# Oscilador.net
KiCad netlist of a schematic drawn in Altium Designer
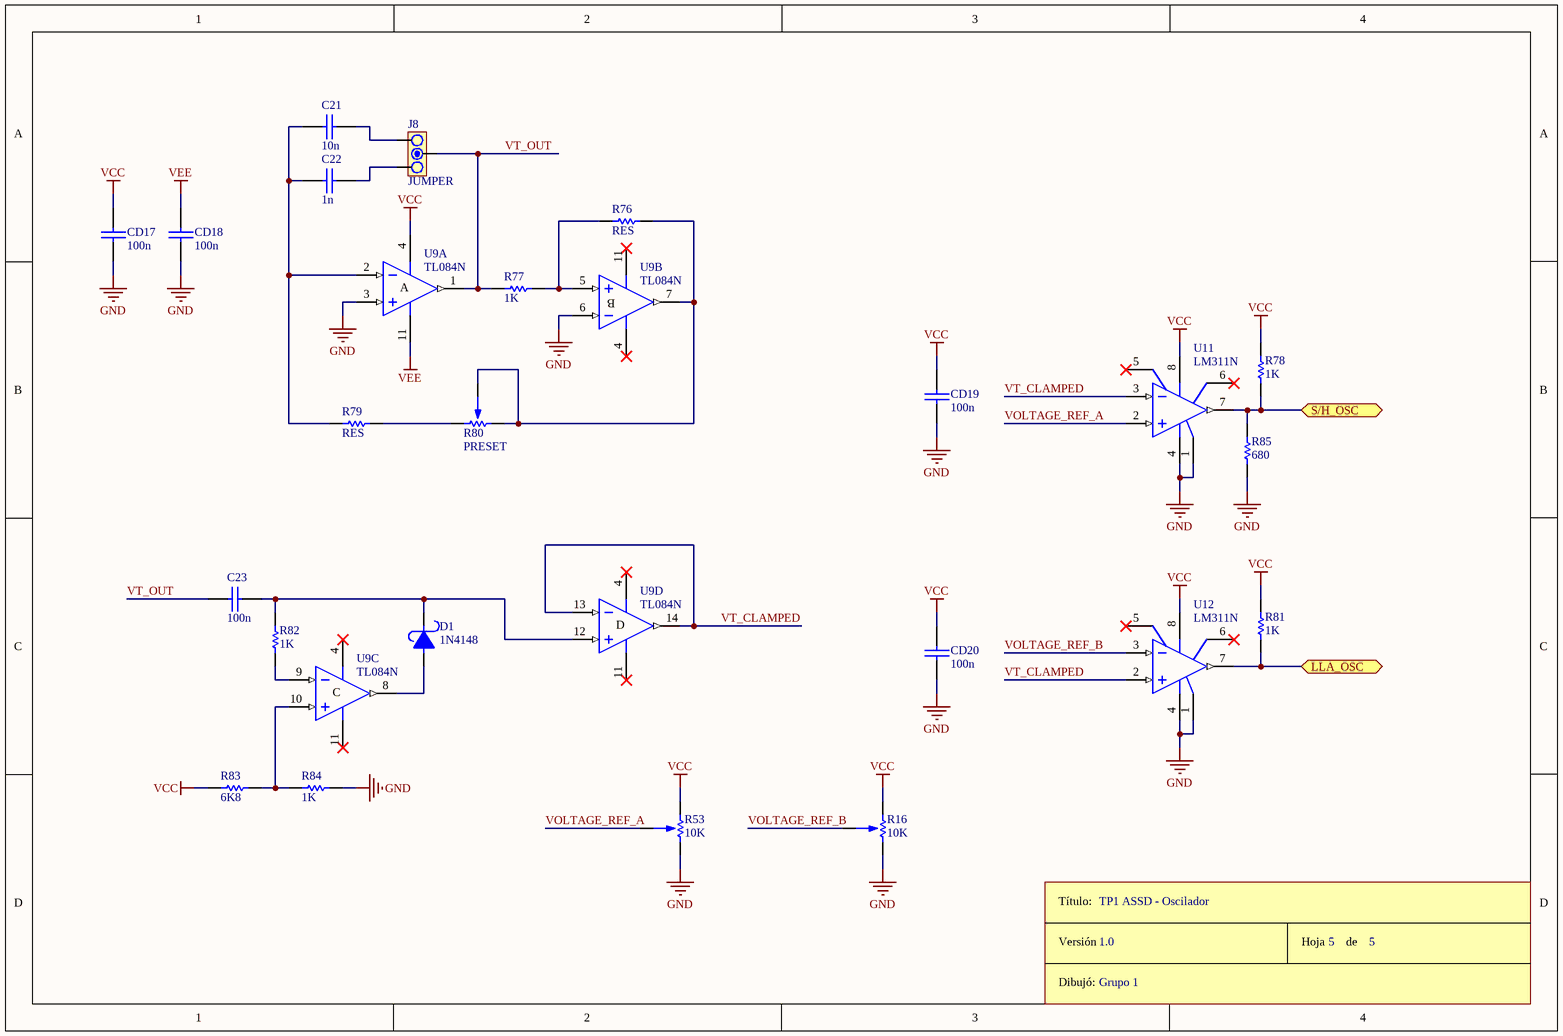
[diagram p0: Oscilador.SchDoc]

(export (version "E")
  (design (tool "Eeschema 10.0.6"))
  (components
    (comp (ref "C21") (value "10n") (footprint "CAP100") (libsource (lib "LIBEBAL") (part "CAP")))
    (comp (ref "C22") (value "1n") (footprint "CAP100") (libsource (lib "LIBEBAL") (part "CAP")))
    (comp (ref "C23") (value "100n") (footprint "CAP100") (libsource (lib "LIBEBAL") (part "CAP")))
    (comp (ref "CD17") (value "100n") (footprint "CAP100") (libsource (lib "LIBEBAL") (part "CAP")))
    (comp (ref "CD18") (value "100n") (footprint "CAP100") (libsource (lib "LIBEBAL") (part "CAP")))
    (comp (ref "CD19") (value "100n") (footprint "CAP100") (libsource (lib "LIBEBAL") (part "CAP")))
    (comp (ref "CD20") (value "100n") (footprint "CAP100") (libsource (lib "LIBEBAL") (part "CAP")))
    (comp (ref "D1") (value "1N4148") (footprint "DO41") (libsource (lib "LIBEBAL") (part "DIODO SCHOTTKY")))
    (comp (ref "J8") (value "JUMPER") (footprint "JUMPER3") (libsource (lib "LIBEBAL") (part "JUMPER3")))
    (comp (ref "R16") (value "10K") (footprint "PRESET V") (libsource (lib "LIBEBAL") (part "PRESET")))
    (comp (ref "R53") (value "10K") (footprint "PRESET V") (libsource (lib "LIBEBAL") (part "PRESET")))
    (comp (ref "R76") (value "RES") (footprint "RES400") (libsource (lib "LIBEBAL") (part "RES")))
    (comp (ref "R77") (value "1K") (footprint "RES400") (libsource (lib "LIBEBAL") (part "RES")))
    (comp (ref "R78") (value "1K") (footprint "RES400") (libsource (lib "LIBEBAL") (part "RES")))
    (comp (ref "R79") (value "RES") (footprint "RES400") (libsource (lib "LIBEBAL") (part "RES")))
    (comp (ref "R80") (value "PRESET") (footprint "PRESET V") (libsource (lib "LIBEBAL") (part "PRESET")))
    (comp (ref "R81") (value "1K") (footprint "RES400") (libsource (lib "LIBEBAL") (part "RES")))
    (comp (ref "R82") (value "1K") (footprint "RES400") (libsource (lib "LIBEBAL") (part "RES")))
    (comp (ref "R83") (value "6K8") (footprint "RES400") (libsource (lib "LIBEBAL") (part "RES")))
    (comp (ref "R84") (value "1K") (footprint "RES400") (libsource (lib "LIBEBAL") (part "RES")))
    (comp (ref "R85") (value "680") (footprint "RES400") (libsource (lib "LIBEBAL") (part "RES")))
    (comp (ref "ROT5") (value "Rótulo") (libsource (lib "LIB PIO IX") (part "Rótulo")))
    (comp (ref "U9")
      (value "TL084N")
      (footprint "N014")
      (description "JFET-Input Operational Amplifier")
      (fields (field (name "PUBLISHER") "Altium Limited"))
      (libsource (lib "TI Operational Amplifier") (part "TL084N"))
    )
    (comp (ref "U11")
      (value "LM311N")
      (footprint "626-05")
      (description "High-Performance Voltage Comparator")
      (fields (field (name "PUBLISHER") "Altium Limited"))
      (libsource (lib "Motorola Analog Comparator") (part "LM311N"))
    )
    (comp (ref "U12")
      (value "LM311N")
      (footprint "626-05")
      (description "High-Performance Voltage Comparator")
      (fields (field (name "PUBLISHER") "Altium Limited"))
      (libsource (lib "Motorola Analog Comparator") (part "LM311N"))
    )
  )
  (nets
    (net (code "1") (name "/LLA_OSC") (class "Default")
      (node (ref "R81") (pin "1") (pinfunction "1_1") (pintype "passive"))
      (node (ref "U12") (pin "7") (pinfunction "OUT_7") (pintype "output"))
    )
    (net (code "2") (name "/S{slash}H_OSC") (class "Default")
      (node (ref "R78") (pin "1") (pinfunction "1_1") (pintype "passive"))
      (node (ref "R85") (pin "2") (pinfunction "2_2") (pintype "passive"))
      (node (ref "U11") (pin "7") (pinfunction "OUT_7") (pintype "output"))
    )
    (net (code "3") (name "/VOLTAGE_REF_A") (class "Default")
      (node (ref "R53") (pin "2") (pinfunction "2_2") (pintype "passive"))
      (node (ref "U11") (pin "2") (pinfunction "IN+_2") (pintype "input"))
    )
    (net (code "4") (name "/VOLTAGE_REF_B") (class "Default")
      (node (ref "R16") (pin "2") (pinfunction "2_2") (pintype "passive"))
      (node (ref "U12") (pin "3") (pinfunction "IN-_3") (pintype "input"))
    )
    (net (code "5") (name "/VT_CLAMPED") (class "Default")
      (node (ref "U11") (pin "3") (pinfunction "IN-_3") (pintype "input"))
      (node (ref "U12") (pin "2") (pinfunction "IN+_2") (pintype "input"))
      (node (ref "U9") (pin "13") (pinfunction "IN-_13") (pintype "input"))
      (node (ref "U9") (pin "14") (pinfunction "OUT_14") (pintype "output"))
    )
    (net (code "6") (name "/VT_OUT") (class "Default")
      (node (ref "C23") (pin "1") (pinfunction "1_1") (pintype "passive"))
      (node (ref "J8") (pin "2") (pinfunction "2_2") (pintype "passive"))
      (node (ref "R77") (pin "1") (pinfunction "1_1") (pintype "passive"))
      (node (ref "U9") (pin "1") (pinfunction "OUT_1") (pintype "output"))
    )
    (net (code "7") (name "GND") (class "Default")
      (node (ref "CD17") (pin "2") (pinfunction "2_2") (pintype "passive"))
      (node (ref "CD18") (pin "2") (pinfunction "2_2") (pintype "passive"))
      (node (ref "CD19") (pin "2") (pinfunction "2_2") (pintype "passive"))
      (node (ref "CD20") (pin "2") (pinfunction "2_2") (pintype "passive"))
      (node (ref "R16") (pin "1") (pinfunction "1_1") (pintype "passive"))
      (node (ref "R53") (pin "1") (pinfunction "1_1") (pintype "passive"))
      (node (ref "R84") (pin "2") (pinfunction "2_2") (pintype "passive"))
      (node (ref "R85") (pin "1") (pinfunction "1_1") (pintype "passive"))
      (node (ref "U11") (pin "1") (pinfunction "GND_1") (pintype "power_in"))
      (node (ref "U11") (pin "4") (pinfunction "V-_4") (pintype "power_in"))
      (node (ref "U12") (pin "1") (pinfunction "GND_1") (pintype "power_in"))
      (node (ref "U12") (pin "4") (pinfunction "V-_4") (pintype "power_in"))
      (node (ref "U9") (pin "3") (pinfunction "IN+_3") (pintype "input"))
      (node (ref "U9") (pin "6") (pinfunction "IN-_6") (pintype "input"))
    )
    (net (code "8") (name "Net-(C21-Pad2)") (class "Default")
      (node (ref "C21") (pin "2") (pinfunction "2_2") (pintype "passive"))
      (node (ref "J8") (pin "3") (pinfunction "3_3") (pintype "passive"))
    )
    (net (code "9") (name "Net-(C22-Pad2)") (class "Default")
      (node (ref "C22") (pin "2") (pinfunction "2_2") (pintype "passive"))
      (node (ref "J8") (pin "1") (pinfunction "1_1") (pintype "passive"))
    )
    (net (code "10") (name "Net-(R79-Pad2)") (class "Default")
      (node (ref "R79") (pin "2") (pinfunction "2_2") (pintype "passive"))
      (node (ref "R80") (pin "1") (pinfunction "1_1") (pintype "passive"))
    )
    (net (code "11") (name "Net-(U9A-IN-)") (class "Default")
      (node (ref "C21") (pin "1") (pinfunction "1_1") (pintype "passive"))
      (node (ref "C22") (pin "1") (pinfunction "1_1") (pintype "passive"))
      (node (ref "R79") (pin "1") (pinfunction "1_1") (pintype "passive"))
      (node (ref "U9") (pin "2") (pinfunction "IN-_2") (pintype "input"))
    )
    (net (code "12") (name "Net-(U9B-IN+)") (class "Default")
      (node (ref "R76") (pin "1") (pinfunction "1_1") (pintype "passive"))
      (node (ref "R77") (pin "2") (pinfunction "2_2") (pintype "passive"))
      (node (ref "U9") (pin "5") (pinfunction "IN+_5") (pintype "input"))
    )
    (net (code "13") (name "Net-(U9B-OUT)") (class "Default")
      (node (ref "R76") (pin "2") (pinfunction "2_2") (pintype "passive"))
      (node (ref "R80") (pin "2") (pinfunction "2_2") (pintype "passive"))
      (node (ref "R80") (pin "3") (pinfunction "3_3") (pintype "passive"))
      (node (ref "U9") (pin "7") (pinfunction "OUT_7") (pintype "output"))
    )
    (net (code "14") (name "Net-(U9C-IN+)") (class "Default")
      (node (ref "R83") (pin "2") (pinfunction "2_2") (pintype "passive"))
      (node (ref "R84") (pin "1") (pinfunction "1_1") (pintype "passive"))
      (node (ref "U9") (pin "10") (pinfunction "IN+_10") (pintype "input"))
    )
    (net (code "15") (name "Net-(U9C-IN-)") (class "Default")
      (node (ref "R82") (pin "1") (pinfunction "1_1") (pintype "passive"))
      (node (ref "U9") (pin "9") (pinfunction "IN-_9") (pintype "input"))
    )
    (net (code "16") (name "Net-(U9C-OUT)") (class "Default")
      (node (ref "D1") (pin "1") (pinfunction "1_1") (pintype "passive"))
      (node (ref "U9") (pin "8") (pinfunction "OUT_8") (pintype "output"))
    )
    (net (code "17") (name "Net-(U9D-IN+)") (class "Default")
      (node (ref "C23") (pin "2") (pinfunction "2_2") (pintype "passive"))
      (node (ref "D1") (pin "2") (pinfunction "2_2") (pintype "passive"))
      (node (ref "R82") (pin "2") (pinfunction "2_2") (pintype "passive"))
      (node (ref "U9") (pin "12") (pinfunction "IN+_12") (pintype "input"))
    )
    (net (code "18") (name "VCC") (class "Default")
      (node (ref "CD17") (pin "1") (pinfunction "1_1") (pintype "passive"))
      (node (ref "CD19") (pin "1") (pinfunction "1_1") (pintype "passive"))
      (node (ref "CD20") (pin "1") (pinfunction "1_1") (pintype "passive"))
      (node (ref "R16") (pin "3") (pinfunction "3_3") (pintype "passive"))
      (node (ref "R53") (pin "3") (pinfunction "3_3") (pintype "passive"))
      (node (ref "R78") (pin "2") (pinfunction "2_2") (pintype "passive"))
      (node (ref "R81") (pin "2") (pinfunction "2_2") (pintype "passive"))
      (node (ref "R83") (pin "1") (pinfunction "1_1") (pintype "passive"))
      (node (ref "U11") (pin "8") (pinfunction "V+_8") (pintype "power_in"))
      (node (ref "U12") (pin "8") (pinfunction "V+_8") (pintype "power_in"))
      (node (ref "U9") (pin "4") (pinfunction "V+_4") (pintype "power_in"))
    )
    (net (code "19") (name "VEE") (class "Default")
      (node (ref "CD18") (pin "1") (pinfunction "1_1") (pintype "passive"))
      (node (ref "U9") (pin "11") (pinfunction "V-_11") (pintype "power_in"))
    )
    (net (code "20") (name "unconnected-(U9B-V+-Pad4)") (class "Default")
      (node (ref "U9") (pin "4") (pinfunction "V+_4") (pintype "power_in+no_connect"))
    )
    (net (code "21") (name "unconnected-(U9B-V--Pad11)") (class "Default")
      (node (ref "U9") (pin "11") (pinfunction "V-_11") (pintype "power_in+no_connect"))
    )
    (net (code "22") (name "unconnected-(U9C-V+-Pad4)") (class "Default")
      (node (ref "U9") (pin "4") (pinfunction "V+_4") (pintype "power_in+no_connect"))
    )
    (net (code "23") (name "unconnected-(U9C-V--Pad11)") (class "Default")
      (node (ref "U9") (pin "11") (pinfunction "V-_11") (pintype "power_in+no_connect"))
    )
    (net (code "24") (name "unconnected-(U9D-V+-Pad4)") (class "Default")
      (node (ref "U9") (pin "4") (pinfunction "V+_4") (pintype "power_in+no_connect"))
    )
    (net (code "25") (name "unconnected-(U9D-V--Pad11)") (class "Default")
      (node (ref "U9") (pin "11") (pinfunction "V-_11") (pintype "power_in+no_connect"))
    )
    (net (code "26") (name "unconnected-(U11-BAL-Pad5)") (class "Default")
      (node (ref "U11") (pin "5") (pinfunction "BAL_5") (pintype "passive+no_connect"))
    )
    (net (code "27") (name "unconnected-(U11-BAL{slash}STB-Pad6)") (class "Default")
      (node (ref "U11") (pin "6") (pinfunction "BAL/STB_6") (pintype "passive+no_connect"))
    )
    (net (code "28") (name "unconnected-(U12-BAL-Pad5)") (class "Default")
      (node (ref "U12") (pin "5") (pinfunction "BAL_5") (pintype "passive+no_connect"))
    )
    (net (code "29") (name "unconnected-(U12-BAL{slash}STB-Pad6)") (class "Default")
      (node (ref "U12") (pin "6") (pinfunction "BAL/STB_6") (pintype "passive+no_connect"))
    )
  )
)
